# M119C.net
KiCad netlist of a schematic drawn in EAGLE
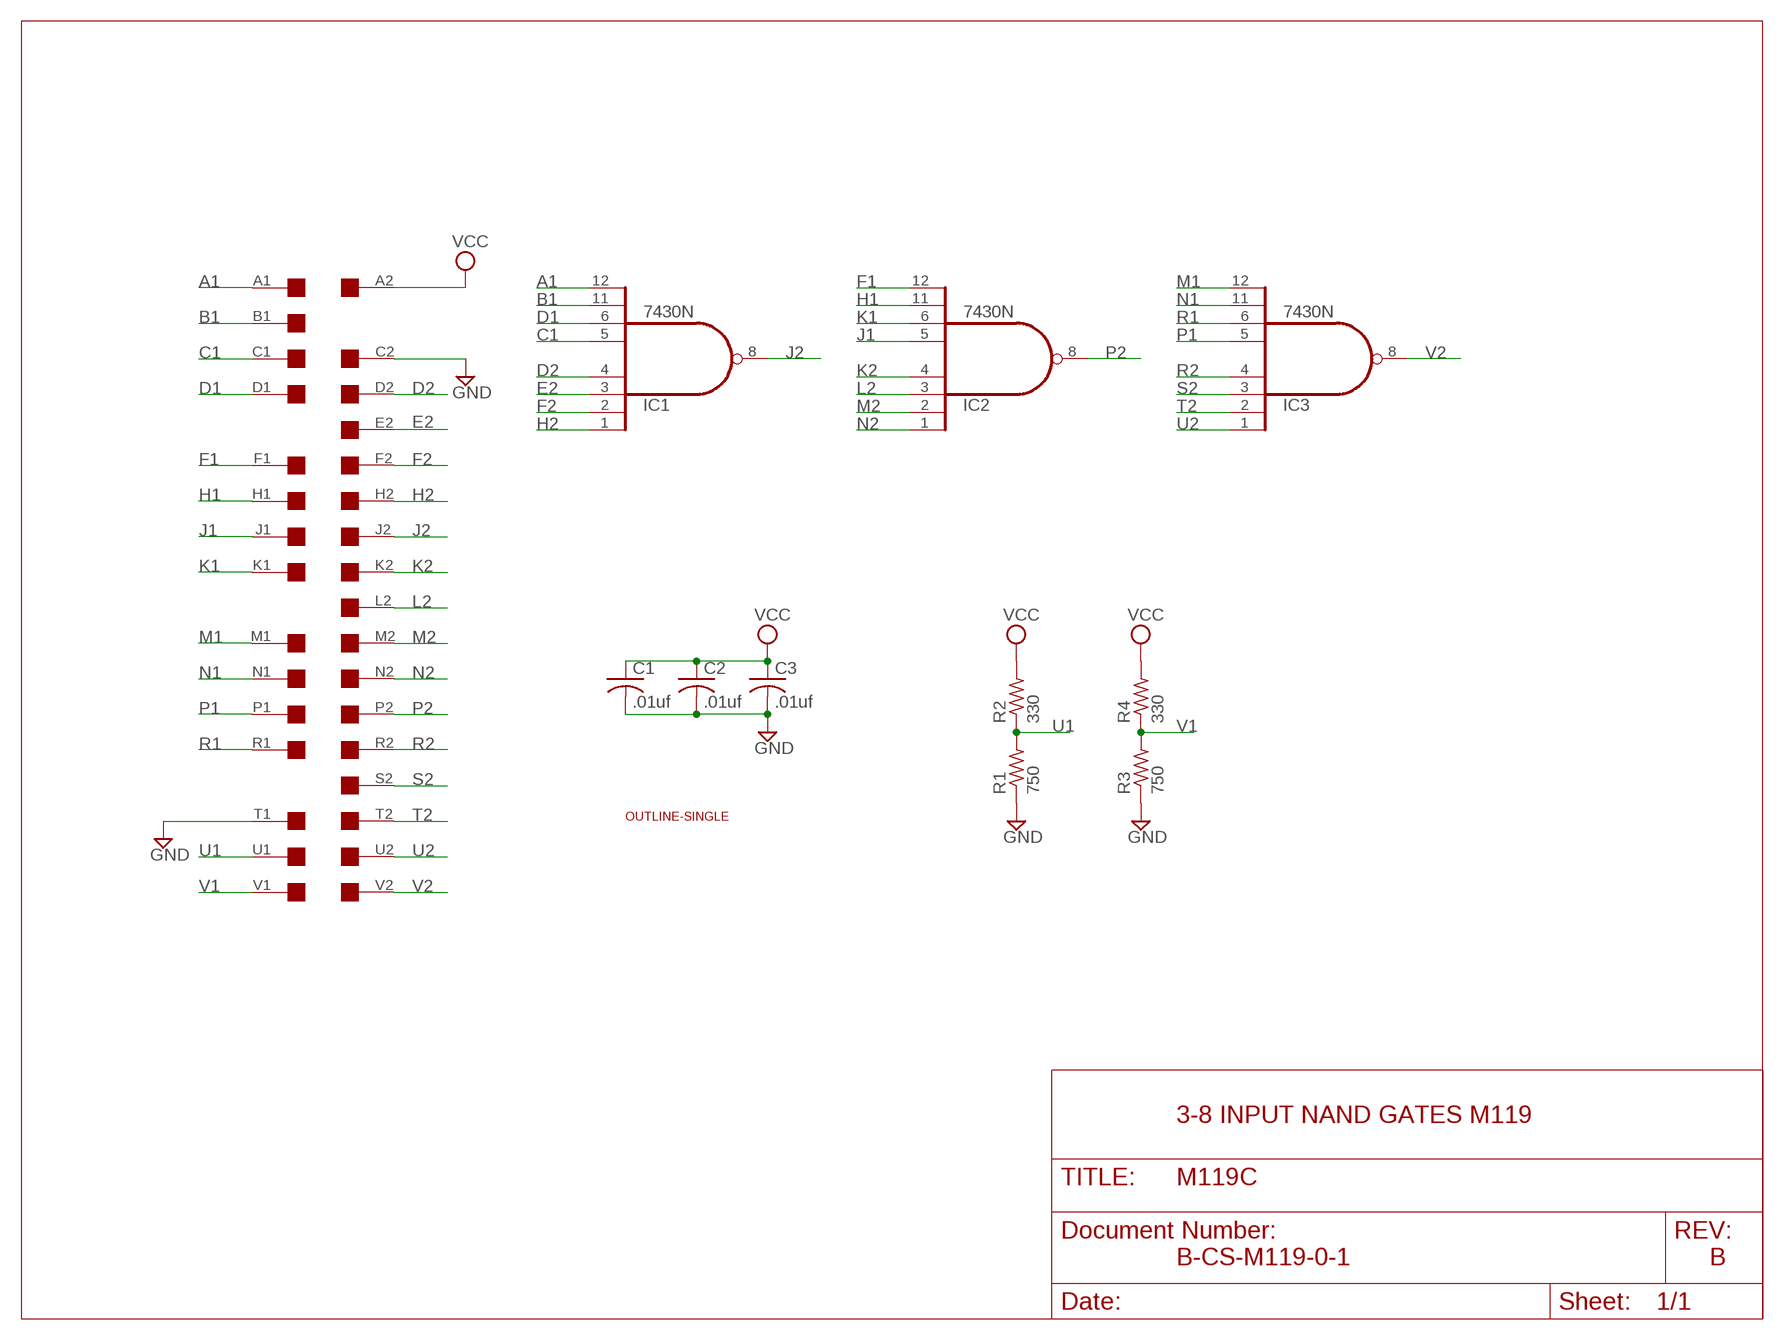
[diagram p0: schematic, sheet 1]

(export (version "E")
  (design (tool "Eeschema 10.0.6"))
  (components
    (comp (ref "C1")
      (value ".01uf")
      (footprint "eagle-import:C050-025X075")
      (libsource (lib "eagle-import") (part "C-US050-025X075"))
    )
    (comp (ref "C2")
      (value ".01uf")
      (footprint "eagle-import:C050-025X075")
      (libsource (lib "eagle-import") (part "C-US050-025X075"))
    )
    (comp (ref "C3")
      (value ".01uf")
      (footprint "eagle-import:C050-025X075")
      (libsource (lib "eagle-import") (part "C-US050-025X075"))
    )
    (comp (ref "IC1")
      (value "7430N")
      (footprint "eagle-import:DIL14")
      (libsource (lib "eagle-import") (part "7430N"))
    )
    (comp (ref "IC2")
      (value "7430N")
      (footprint "eagle-import:DIL14")
      (libsource (lib "eagle-import") (part "7430N"))
    )
    (comp (ref "IC3")
      (value "7430N")
      (footprint "eagle-import:DIL14")
      (libsource (lib "eagle-import") (part "7430N"))
    )
    (comp (ref "R1")
      (value "750")
      (footprint "eagle-import:0207_10")
      (libsource (lib "eagle-import") (part "R-US_0207/10"))
    )
    (comp (ref "R2")
      (value "330")
      (footprint "eagle-import:0207_10")
      (libsource (lib "eagle-import") (part "R-US_0207/10"))
    )
    (comp (ref "R3")
      (value "750")
      (footprint "eagle-import:0207_10")
      (libsource (lib "eagle-import") (part "R-US_0207/10"))
    )
    (comp (ref "R4")
      (value "330")
      (footprint "eagle-import:0207_10")
      (libsource (lib "eagle-import") (part "R-US_0207/10"))
    )
    (comp (ref "U$1")
      (value "OUTLINE-SINGLE")
      (footprint "eagle-import:SINGLE")
      (libsource (lib "eagle-import") (part "OUTLINE-SINGLE"))
    )
    (comp (ref "U$4")
      (value "SINGLE")
      (footprint "eagle-import:EDGE-CON2")
      (libsource (lib "eagle-import") (part "SINGLE"))
    )
  )
  (nets
    (net (code "1") (name "/A1") (class "Default")
      (node (ref "IC1") (pin "12") (pinfunction "I7_12") (pintype "input"))
      (node (ref "U$4") (pin "A1") (pinfunction "1_A1") (pintype "bidirectional"))
    )
    (net (code "2") (name "/B1") (class "Default")
      (node (ref "IC1") (pin "11") (pinfunction "I6_11") (pintype "input"))
      (node (ref "U$4") (pin "B1") (pinfunction "1_B1") (pintype "bidirectional"))
    )
    (net (code "3") (name "/C1") (class "Default")
      (node (ref "IC1") (pin "5") (pinfunction "I4_5") (pintype "input"))
      (node (ref "U$4") (pin "C1") (pinfunction "1_C1") (pintype "bidirectional"))
    )
    (net (code "4") (name "/D1") (class "Default")
      (node (ref "IC1") (pin "6") (pinfunction "I5_6") (pintype "input"))
      (node (ref "U$4") (pin "D1") (pinfunction "1_D1") (pintype "bidirectional"))
    )
    (net (code "5") (name "/D2") (class "Default")
      (node (ref "IC1") (pin "4") (pinfunction "I3_4") (pintype "input"))
      (node (ref "U$4") (pin "D2") (pinfunction "1_D2") (pintype "bidirectional"))
    )
    (net (code "6") (name "/E2") (class "Default")
      (node (ref "IC1") (pin "3") (pinfunction "I2_3") (pintype "input"))
      (node (ref "U$4") (pin "E2") (pinfunction "1_E2") (pintype "bidirectional"))
    )
    (net (code "7") (name "/F1") (class "Default")
      (node (ref "IC2") (pin "12") (pinfunction "I7_12") (pintype "input"))
      (node (ref "U$4") (pin "F1") (pinfunction "1_F1") (pintype "bidirectional"))
    )
    (net (code "8") (name "/F2") (class "Default")
      (node (ref "IC1") (pin "2") (pinfunction "I1_2") (pintype "input"))
      (node (ref "U$4") (pin "F2") (pinfunction "1_F2") (pintype "bidirectional"))
    )
    (net (code "9") (name "/H1") (class "Default")
      (node (ref "IC2") (pin "11") (pinfunction "I6_11") (pintype "input"))
      (node (ref "U$4") (pin "H1") (pinfunction "1_H1") (pintype "bidirectional"))
    )
    (net (code "10") (name "/H2") (class "Default")
      (node (ref "IC1") (pin "1") (pinfunction "I0_1") (pintype "input"))
      (node (ref "U$4") (pin "H2") (pinfunction "1_H2") (pintype "bidirectional"))
    )
    (net (code "11") (name "/J1") (class "Default")
      (node (ref "IC2") (pin "5") (pinfunction "I4_5") (pintype "input"))
      (node (ref "U$4") (pin "J1") (pinfunction "1_J1") (pintype "bidirectional"))
    )
    (net (code "12") (name "/J2") (class "Default")
      (node (ref "IC1") (pin "8") (pinfunction "O_8") (pintype "output"))
      (node (ref "U$4") (pin "J2") (pinfunction "1_J2") (pintype "bidirectional"))
    )
    (net (code "13") (name "/K1") (class "Default")
      (node (ref "IC2") (pin "6") (pinfunction "I5_6") (pintype "input"))
      (node (ref "U$4") (pin "K1") (pinfunction "1_K1") (pintype "bidirectional"))
    )
    (net (code "14") (name "/K2") (class "Default")
      (node (ref "IC2") (pin "4") (pinfunction "I3_4") (pintype "input"))
      (node (ref "U$4") (pin "K2") (pinfunction "1_K2") (pintype "bidirectional"))
    )
    (net (code "15") (name "/L2") (class "Default")
      (node (ref "IC2") (pin "3") (pinfunction "I2_3") (pintype "input"))
      (node (ref "U$4") (pin "L2") (pinfunction "1_L2") (pintype "bidirectional"))
    )
    (net (code "16") (name "/M1") (class "Default")
      (node (ref "IC3") (pin "12") (pinfunction "I7_12") (pintype "input"))
      (node (ref "U$4") (pin "M1") (pinfunction "1_M1") (pintype "bidirectional"))
    )
    (net (code "17") (name "/M2") (class "Default")
      (node (ref "IC2") (pin "2") (pinfunction "I1_2") (pintype "input"))
      (node (ref "U$4") (pin "M2") (pinfunction "1_M2") (pintype "bidirectional"))
    )
    (net (code "18") (name "/N1") (class "Default")
      (node (ref "IC3") (pin "11") (pinfunction "I6_11") (pintype "input"))
      (node (ref "U$4") (pin "N1") (pinfunction "1_N1") (pintype "bidirectional"))
    )
    (net (code "19") (name "/N2") (class "Default")
      (node (ref "IC2") (pin "1") (pinfunction "I0_1") (pintype "input"))
      (node (ref "U$4") (pin "N2") (pinfunction "1_N2") (pintype "bidirectional"))
    )
    (net (code "20") (name "/P1") (class "Default")
      (node (ref "IC3") (pin "5") (pinfunction "I4_5") (pintype "input"))
      (node (ref "U$4") (pin "P1") (pinfunction "1_P1") (pintype "bidirectional"))
    )
    (net (code "21") (name "/P2") (class "Default")
      (node (ref "IC2") (pin "8") (pinfunction "O_8") (pintype "output"))
      (node (ref "U$4") (pin "P2") (pinfunction "1_P2") (pintype "bidirectional"))
    )
    (net (code "22") (name "/R1") (class "Default")
      (node (ref "IC3") (pin "6") (pinfunction "I5_6") (pintype "input"))
      (node (ref "U$4") (pin "R1") (pinfunction "1_R1") (pintype "bidirectional"))
    )
    (net (code "23") (name "/R2") (class "Default")
      (node (ref "IC3") (pin "4") (pinfunction "I3_4") (pintype "input"))
      (node (ref "U$4") (pin "R2") (pinfunction "1_R2") (pintype "bidirectional"))
    )
    (net (code "24") (name "/S2") (class "Default")
      (node (ref "IC3") (pin "3") (pinfunction "I2_3") (pintype "input"))
      (node (ref "U$4") (pin "S2") (pinfunction "1_S2") (pintype "bidirectional"))
    )
    (net (code "25") (name "/T2") (class "Default")
      (node (ref "IC3") (pin "2") (pinfunction "I1_2") (pintype "input"))
      (node (ref "U$4") (pin "T2") (pinfunction "1_T2") (pintype "bidirectional"))
    )
    (net (code "26") (name "/U1") (class "Default")
      (node (ref "R1") (pin "2") (pinfunction "2_2") (pintype "passive"))
      (node (ref "R2") (pin "1") (pinfunction "1_1") (pintype "passive"))
      (node (ref "U$4") (pin "U1") (pinfunction "1_U1") (pintype "bidirectional"))
    )
    (net (code "27") (name "/U2") (class "Default")
      (node (ref "IC3") (pin "1") (pinfunction "I0_1") (pintype "input"))
      (node (ref "U$4") (pin "U2") (pinfunction "1_U2") (pintype "bidirectional"))
    )
    (net (code "28") (name "/V1") (class "Default")
      (node (ref "R3") (pin "2") (pinfunction "2_2") (pintype "passive"))
      (node (ref "R4") (pin "1") (pinfunction "1_1") (pintype "passive"))
      (node (ref "U$4") (pin "V1") (pinfunction "1_V1") (pintype "bidirectional"))
    )
    (net (code "29") (name "/V2") (class "Default")
      (node (ref "IC3") (pin "8") (pinfunction "O_8") (pintype "output"))
      (node (ref "U$4") (pin "V2") (pinfunction "1_V2") (pintype "bidirectional"))
    )
    (net (code "30") (name "GND") (class "Default")
      (node (ref "C1") (pin "2") (pinfunction "2_2") (pintype "passive"))
      (node (ref "C2") (pin "2") (pinfunction "2_2") (pintype "passive"))
      (node (ref "C3") (pin "2") (pinfunction "2_2") (pintype "passive"))
      (node (ref "R1") (pin "1") (pinfunction "1_1") (pintype "passive"))
      (node (ref "R3") (pin "1") (pinfunction "1_1") (pintype "passive"))
      (node (ref "U$4") (pin "C2") (pinfunction "1_C2") (pintype "bidirectional"))
      (node (ref "U$4") (pin "T1") (pinfunction "1_T1") (pintype "bidirectional"))
    )
    (net (code "31") (name "VCC") (class "Default")
      (node (ref "C1") (pin "1") (pinfunction "1_1") (pintype "passive"))
      (node (ref "C2") (pin "1") (pinfunction "1_1") (pintype "passive"))
      (node (ref "C3") (pin "1") (pinfunction "1_1") (pintype "passive"))
      (node (ref "R2") (pin "2") (pinfunction "2_2") (pintype "passive"))
      (node (ref "R4") (pin "2") (pinfunction "2_2") (pintype "passive"))
      (node (ref "U$4") (pin "A2") (pinfunction "1_A2") (pintype "bidirectional"))
    )
  )
)
